# PressureSensors.net
KiCad netlist of a schematic drawn in Altium Designer
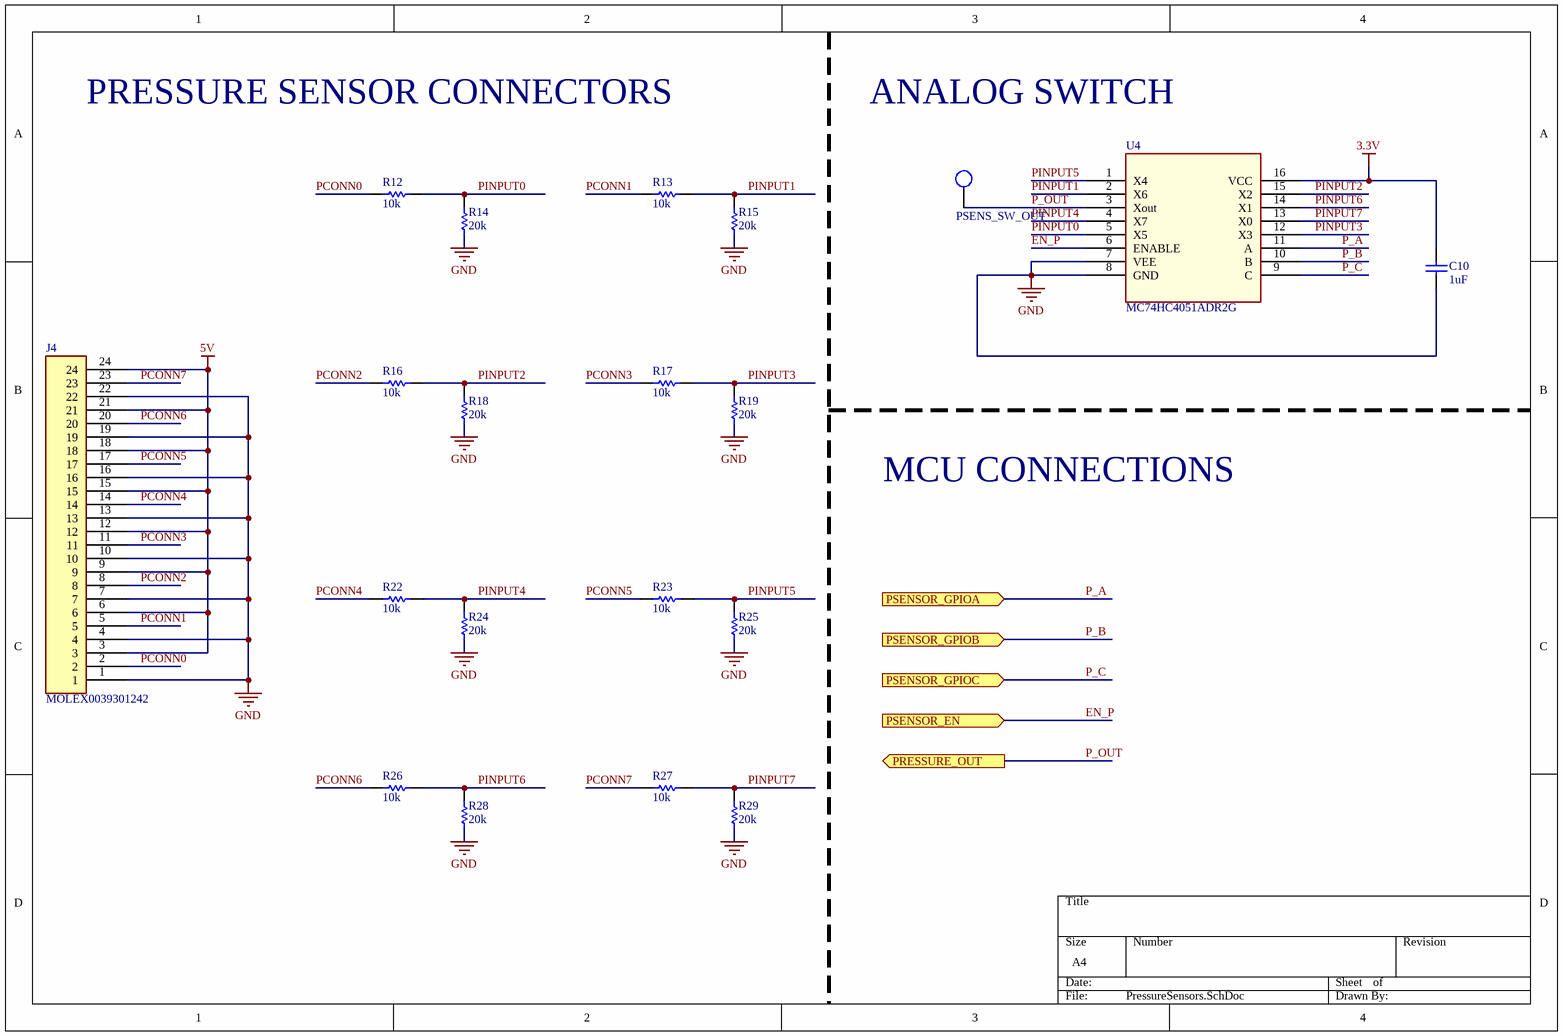
[diagram p0: PressureSensors.SchDoc]

(export (version "E")
  (design (tool "Eeschema 10.0.6"))
  (components
    (comp (ref "C10")
      (value "1uF")
      (footprint "0603 - Capacitor")
      (description "Nonpolarized Capacitor")
      (fields (field (name "Comment") "Capacitor - Nonpolarized"))
      (libsource (lib "General") (part "Capacitor - Nonpolarized"))
    )
    (comp (ref "J4")
      (value "MOLEX0039301242")
      (footprint "MOLEX0039301242")
      (description "Connector Header Through Hole, Right Angle 24 position 0.165\" (4.20mm)")
      (fields (field (name "MANUFACTURER") "Molex") (field (name "MANUFACTURER PART NUMBER") "0039301082"))
      (libsource (lib "GeneralConnectors") (part "MOLEX0039301242"))
    )
    (comp (ref "PSENS_SW_OUT")
      (value "Test Point")
      (footprint "Test Point - 5002")
      (libsource (lib "General") (part "Test Point"))
    )
    (comp (ref "R12")
      (value "10k")
      (footprint "0805 - Resistor")
      (description "Resistor")
      (libsource (lib "General") (part "Resistor"))
    )
    (comp (ref "R13")
      (value "10k")
      (footprint "0805 - Resistor")
      (description "Resistor")
      (libsource (lib "General") (part "Resistor"))
    )
    (comp (ref "R14")
      (value "20k")
      (footprint "0805 - Resistor")
      (description "Resistor")
      (libsource (lib "General") (part "Resistor"))
    )
    (comp (ref "R15")
      (value "20k")
      (footprint "0805 - Resistor")
      (description "Resistor")
      (libsource (lib "General") (part "Resistor"))
    )
    (comp (ref "R16")
      (value "10k")
      (footprint "0805 - Resistor")
      (description "Resistor")
      (libsource (lib "General") (part "Resistor"))
    )
    (comp (ref "R17")
      (value "10k")
      (footprint "0805 - Resistor")
      (description "Resistor")
      (libsource (lib "General") (part "Resistor"))
    )
    (comp (ref "R18")
      (value "20k")
      (footprint "0805 - Resistor")
      (description "Resistor")
      (libsource (lib "General") (part "Resistor"))
    )
    (comp (ref "R19")
      (value "20k")
      (footprint "0805 - Resistor")
      (description "Resistor")
      (libsource (lib "General") (part "Resistor"))
    )
    (comp (ref "R22")
      (value "10k")
      (footprint "0805 - Resistor")
      (description "Resistor")
      (libsource (lib "General") (part "Resistor"))
    )
    (comp (ref "R23")
      (value "10k")
      (footprint "0805 - Resistor")
      (description "Resistor")
      (libsource (lib "General") (part "Resistor"))
    )
    (comp (ref "R24")
      (value "20k")
      (footprint "0805 - Resistor")
      (description "Resistor")
      (libsource (lib "General") (part "Resistor"))
    )
    (comp (ref "R25")
      (value "20k")
      (footprint "0805 - Resistor")
      (description "Resistor")
      (libsource (lib "General") (part "Resistor"))
    )
    (comp (ref "R26")
      (value "10k")
      (footprint "0805 - Resistor")
      (description "Resistor")
      (libsource (lib "General") (part "Resistor"))
    )
    (comp (ref "R27")
      (value "10k")
      (footprint "0805 - Resistor")
      (description "Resistor")
      (libsource (lib "General") (part "Resistor"))
    )
    (comp (ref "R28")
      (value "20k")
      (footprint "0805 - Resistor")
      (description "Resistor")
      (libsource (lib "General") (part "Resistor"))
    )
    (comp (ref "R29")
      (value "20k")
      (footprint "0805 - Resistor")
      (description "Resistor")
      (libsource (lib "General") (part "Resistor"))
    )
    (comp (ref "U4")
      (value "MC74HC4051ADR2G")
      (footprint "MC74HC4051ADR2G")
      (description "1 Circuit IC Switch 8:1 100Ohm 16-SOIC")
      (libsource (lib "Embedded") (part "MC74HC4051ADR2G"))
    )
  )
  (nets
    (net (code "1") (name "/EN_P") (class "Default")
      (node (ref "U4") (pin "6") (pinfunction "ENABLE_6") (pintype "passive"))
    )
    (net (code "2") (name "/PCONN0") (class "Default")
      (node (ref "J4") (pin "2") (pinfunction "2_2") (pintype "passive"))
      (node (ref "R12") (pin "1") (pinfunction "1_1") (pintype "passive"))
    )
    (net (code "3") (name "/PCONN1") (class "Default")
      (node (ref "J4") (pin "5") (pinfunction "5_5") (pintype "passive"))
      (node (ref "R13") (pin "1") (pinfunction "1_1") (pintype "passive"))
    )
    (net (code "4") (name "/PCONN2") (class "Default")
      (node (ref "J4") (pin "8") (pinfunction "8_8") (pintype "passive"))
      (node (ref "R16") (pin "1") (pinfunction "1_1") (pintype "passive"))
    )
    (net (code "5") (name "/PCONN3") (class "Default")
      (node (ref "J4") (pin "11") (pinfunction "11_11") (pintype "passive"))
      (node (ref "R17") (pin "1") (pinfunction "1_1") (pintype "passive"))
    )
    (net (code "6") (name "/PCONN4") (class "Default")
      (node (ref "J4") (pin "14") (pinfunction "14_14") (pintype "passive"))
      (node (ref "R22") (pin "1") (pinfunction "1_1") (pintype "passive"))
    )
    (net (code "7") (name "/PCONN5") (class "Default")
      (node (ref "J4") (pin "17") (pinfunction "17_17") (pintype "passive"))
      (node (ref "R23") (pin "1") (pinfunction "1_1") (pintype "passive"))
    )
    (net (code "8") (name "/PCONN6") (class "Default")
      (node (ref "J4") (pin "20") (pinfunction "20_20") (pintype "passive"))
      (node (ref "R26") (pin "1") (pinfunction "1_1") (pintype "passive"))
    )
    (net (code "9") (name "/PCONN7") (class "Default")
      (node (ref "J4") (pin "23") (pinfunction "23_23") (pintype "passive"))
      (node (ref "R27") (pin "1") (pinfunction "1_1") (pintype "passive"))
    )
    (net (code "10") (name "/PINPUT0") (class "Default")
      (node (ref "R12") (pin "2") (pinfunction "2_2") (pintype "passive"))
      (node (ref "R14") (pin "2") (pinfunction "2_2") (pintype "passive"))
      (node (ref "U4") (pin "5") (pinfunction "X5_5") (pintype "passive"))
    )
    (net (code "11") (name "/PINPUT1") (class "Default")
      (node (ref "R13") (pin "2") (pinfunction "2_2") (pintype "passive"))
      (node (ref "R15") (pin "2") (pinfunction "2_2") (pintype "passive"))
      (node (ref "U4") (pin "2") (pinfunction "X6_2") (pintype "passive"))
    )
    (net (code "12") (name "/PINPUT2") (class "Default")
      (node (ref "R16") (pin "2") (pinfunction "2_2") (pintype "passive"))
      (node (ref "R18") (pin "2") (pinfunction "2_2") (pintype "passive"))
      (node (ref "U4") (pin "15") (pinfunction "X2_15") (pintype "passive"))
    )
    (net (code "13") (name "/PINPUT3") (class "Default")
      (node (ref "R17") (pin "2") (pinfunction "2_2") (pintype "passive"))
      (node (ref "R19") (pin "2") (pinfunction "2_2") (pintype "passive"))
      (node (ref "U4") (pin "12") (pinfunction "X3_12") (pintype "passive"))
    )
    (net (code "14") (name "/PINPUT4") (class "Default")
      (node (ref "R22") (pin "2") (pinfunction "2_2") (pintype "passive"))
      (node (ref "R24") (pin "2") (pinfunction "2_2") (pintype "passive"))
      (node (ref "U4") (pin "4") (pinfunction "X7_4") (pintype "passive"))
    )
    (net (code "15") (name "/PINPUT5") (class "Default")
      (node (ref "R23") (pin "2") (pinfunction "2_2") (pintype "passive"))
      (node (ref "R25") (pin "2") (pinfunction "2_2") (pintype "passive"))
      (node (ref "U4") (pin "1") (pinfunction "X4_1") (pintype "passive"))
    )
    (net (code "16") (name "/PINPUT6") (class "Default")
      (node (ref "R26") (pin "2") (pinfunction "2_2") (pintype "passive"))
      (node (ref "R28") (pin "2") (pinfunction "2_2") (pintype "passive"))
      (node (ref "U4") (pin "14") (pinfunction "X1_14") (pintype "passive"))
    )
    (net (code "17") (name "/PINPUT7") (class "Default")
      (node (ref "R27") (pin "2") (pinfunction "2_2") (pintype "passive"))
      (node (ref "R29") (pin "2") (pinfunction "2_2") (pintype "passive"))
      (node (ref "U4") (pin "13") (pinfunction "X0_13") (pintype "passive"))
    )
    (net (code "18") (name "/P_A") (class "Default")
      (node (ref "U4") (pin "11") (pinfunction "A_11") (pintype "passive"))
    )
    (net (code "19") (name "/P_B") (class "Default")
      (node (ref "U4") (pin "10") (pinfunction "B_10") (pintype "passive"))
    )
    (net (code "20") (name "/P_C") (class "Default")
      (node (ref "U4") (pin "9") (pinfunction "C_9") (pintype "passive"))
    )
    (net (code "21") (name "/P_OUT") (class "Default")
      (node (ref "PSENS_SW_OUT") (pin "1") (pinfunction "0_1") (pintype "passive"))
      (node (ref "U4") (pin "3") (pinfunction "Xout_3") (pintype "passive"))
    )
    (net (code "22") (name "3.3V") (class "Default")
      (node (ref "C10") (pin "2") (pinfunction "2_2") (pintype "passive"))
      (node (ref "U4") (pin "16") (pinfunction "VCC_16") (pintype "power_in"))
    )
    (net (code "23") (name "5V") (class "Default")
      (node (ref "J4") (pin "12") (pinfunction "12_12") (pintype "passive"))
      (node (ref "J4") (pin "15") (pinfunction "15_15") (pintype "passive"))
      (node (ref "J4") (pin "18") (pinfunction "18_18") (pintype "passive"))
      (node (ref "J4") (pin "21") (pinfunction "21_21") (pintype "passive"))
      (node (ref "J4") (pin "24") (pinfunction "24_24") (pintype "passive"))
      (node (ref "J4") (pin "3") (pinfunction "3_3") (pintype "passive"))
      (node (ref "J4") (pin "6") (pinfunction "6_6") (pintype "passive"))
      (node (ref "J4") (pin "9") (pinfunction "9_9") (pintype "passive"))
    )
    (net (code "24") (name "GND") (class "Default")
      (node (ref "C10") (pin "1") (pinfunction "1_1") (pintype "passive"))
      (node (ref "J4") (pin "1") (pinfunction "1_1") (pintype "passive"))
      (node (ref "J4") (pin "10") (pinfunction "10_10") (pintype "passive"))
      (node (ref "J4") (pin "13") (pinfunction "13_13") (pintype "passive"))
      (node (ref "J4") (pin "16") (pinfunction "16_16") (pintype "passive"))
      (node (ref "J4") (pin "19") (pinfunction "19_19") (pintype "passive"))
      (node (ref "J4") (pin "22") (pinfunction "22_22") (pintype "passive"))
      (node (ref "J4") (pin "4") (pinfunction "4_4") (pintype "passive"))
      (node (ref "J4") (pin "7") (pinfunction "7_7") (pintype "passive"))
      (node (ref "R14") (pin "1") (pinfunction "1_1") (pintype "passive"))
      (node (ref "R15") (pin "1") (pinfunction "1_1") (pintype "passive"))
      (node (ref "R18") (pin "1") (pinfunction "1_1") (pintype "passive"))
      (node (ref "R19") (pin "1") (pinfunction "1_1") (pintype "passive"))
      (node (ref "R24") (pin "1") (pinfunction "1_1") (pintype "passive"))
      (node (ref "R25") (pin "1") (pinfunction "1_1") (pintype "passive"))
      (node (ref "R28") (pin "1") (pinfunction "1_1") (pintype "passive"))
      (node (ref "R29") (pin "1") (pinfunction "1_1") (pintype "passive"))
      (node (ref "U4") (pin "7") (pinfunction "VEE_7") (pintype "power_in"))
      (node (ref "U4") (pin "8") (pinfunction "GND_8") (pintype "power_in"))
    )
  )
)
